# source_eagle.net
KiCad netlist of a schematic drawn in EAGLE
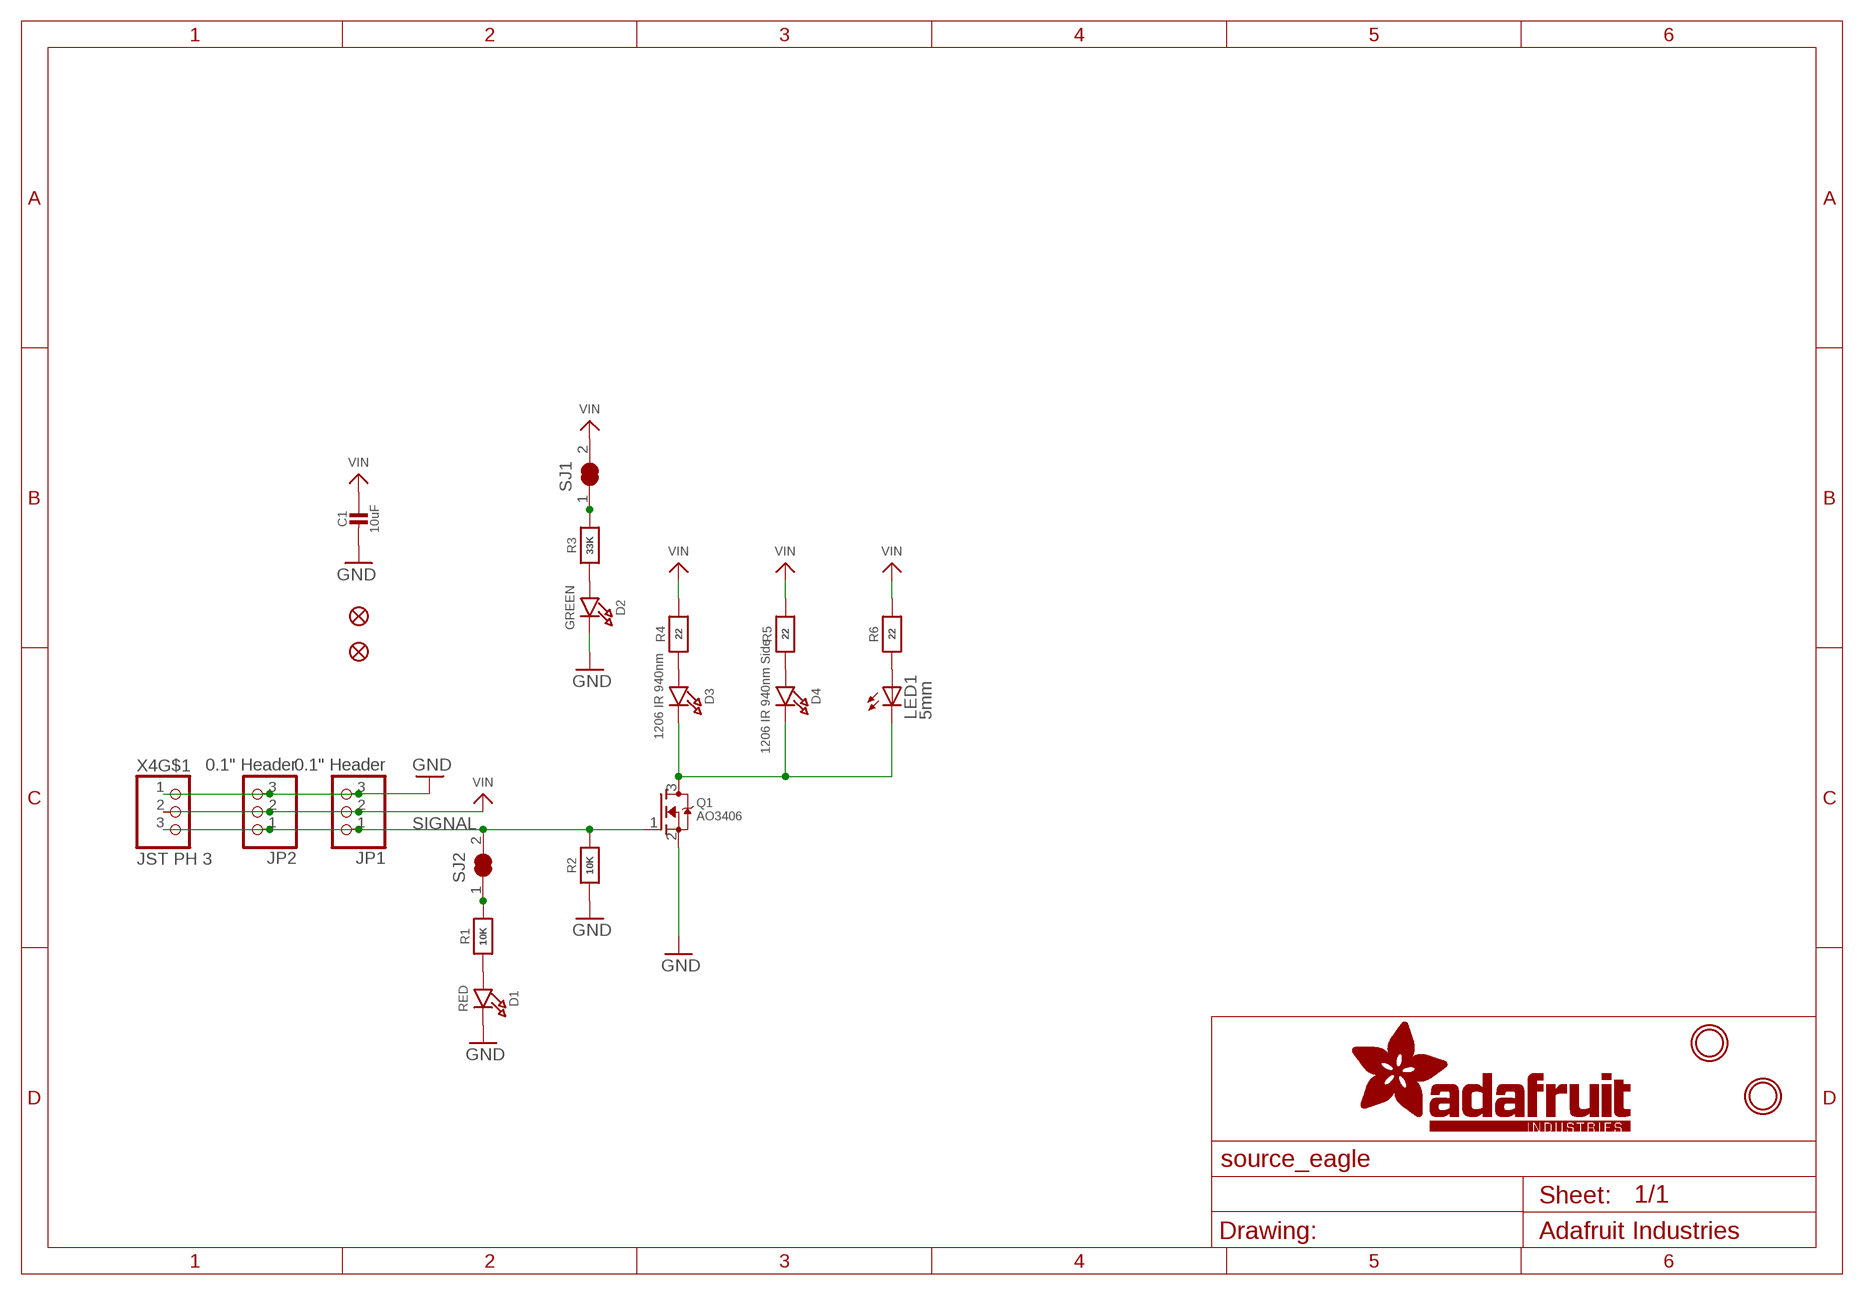
[diagram p0: schematic, sheet 1]

(export (version "E")
  (design (tool "Eeschema 10.0.6"))
  (components
    (comp (ref "C1")
      (value "10uF")
      (footprint "eagle-import:0805-NO")
      (libsource (lib "eagle-import") (part "CAP_CERAMIC0805-NOOUTLINE"))
    )
    (comp (ref "D1")
      (value "RED")
      (footprint "eagle-import:CHIPLED_0603_NOOUTLINE")
      (libsource (lib "eagle-import") (part "LED0603_NOOUTLINE"))
    )
    (comp (ref "D2")
      (value "GREEN")
      (footprint "eagle-import:CHIPLED_0603_NOOUTLINE")
      (libsource (lib "eagle-import") (part "LED0603_NOOUTLINE"))
    )
    (comp (ref "D3")
      (value "1206 IR 940nm")
      (footprint "eagle-import:CHIPLED_1206")
      (libsource (lib "eagle-import") (part "LED1206"))
    )
    (comp (ref "D4")
      (value "1206 IR 940nm Side")
      (footprint "eagle-import:LED_1206_SIDE")
      (libsource (lib "eagle-import") (part "LED_1206RA"))
    )
    (comp (ref "FID2")
      (value "FIDUCIAL_1MM")
      (footprint "eagle-import:FIDUCIAL_1MM")
      (libsource (lib "eagle-import") (part "FIDUCIAL_1MM"))
    )
    (comp (ref "FID3")
      (value "FIDUCIAL_1MM")
      (footprint "eagle-import:FIDUCIAL_1MM")
      (libsource (lib "eagle-import") (part "FIDUCIAL_1MM"))
    )
    (comp (ref "JP1")
      (value "0.1\" Header")
      (footprint "eagle-import:1X03_OVAL")
      (libsource (lib "eagle-import") (part "HEADER-1X3"))
    )
    (comp (ref "JP2")
      (value "0.1\" Header")
      (footprint "eagle-import:1X03_ROUND")
      (libsource (lib "eagle-import") (part "HEADER-1X3ROUND"))
    )
    (comp (ref "LED1")
      (value "5mm")
      (footprint "eagle-import:LED5MM")
      (libsource (lib "eagle-import") (part "LED5MM"))
    )
    (comp (ref "Q1")
      (value "AO3406")
      (footprint "eagle-import:SOT23-WIDE")
      (libsource (lib "eagle-import") (part "MOSFET-NWIDE"))
    )
    (comp (ref "R1")
      (value "10K")
      (footprint "eagle-import:0603-NO")
      (libsource (lib "eagle-import") (part "RESISTOR_0603_NOOUT"))
    )
    (comp (ref "R2")
      (value "10K")
      (footprint "eagle-import:0603-NO")
      (libsource (lib "eagle-import") (part "RESISTOR_0603_NOOUT"))
    )
    (comp (ref "R3")
      (value "33K")
      (footprint "eagle-import:0603-NO")
      (libsource (lib "eagle-import") (part "RESISTOR_0603_NOOUT"))
    )
    (comp (ref "R4")
      (value "22")
      (footprint "eagle-import:0603-NO")
      (libsource (lib "eagle-import") (part "RESISTOR_0603_NOOUT"))
    )
    (comp (ref "R5")
      (value "22")
      (footprint "eagle-import:0603-NO")
      (libsource (lib "eagle-import") (part "RESISTOR_0603_NOOUT"))
    )
    (comp (ref "R6")
      (value "22")
      (footprint "eagle-import:0603-NO")
      (libsource (lib "eagle-import") (part "RESISTOR_0603_NOOUT"))
    )
    (comp (ref "SJ1")
      (value "SOLDERJUMPER_CLOSED")
      (footprint "eagle-import:SOLDERJUMPER_CLOSEDWIRE")
      (libsource (lib "eagle-import") (part "SOLDERJUMPER_CLOSED"))
    )
    (comp (ref "SJ2")
      (value "SOLDERJUMPER_CLOSED")
      (footprint "eagle-import:SOLDERJUMPER_CLOSEDWIRE")
      (libsource (lib "eagle-import") (part "SOLDERJUMPER_CLOSED"))
    )
    (comp (ref "U$1")
      (value "MOUNTINGHOLE2.5")
      (footprint "eagle-import:MOUNTINGHOLE_2.5_PLATED")
      (libsource (lib "eagle-import") (part "MOUNTINGHOLE2.5"))
    )
    (comp (ref "U$8")
      (value "MOUNTINGHOLE2.5")
      (footprint "eagle-import:MOUNTINGHOLE_2.5_PLATED")
      (libsource (lib "eagle-import") (part "MOUNTINGHOLE2.5"))
    )
    (comp (ref "X4")
      (value "JST PH 3")
      (footprint "eagle-import:JSTPH3")
      (libsource (lib "eagle-import") (part "CON_JST_PH_3PIN"))
    )
  )
  (nets
    (net (code "1") (name "/SIGNAL") (class "Default")
      (node (ref "JP1") (pin "1") (pinfunction "1_1") (pintype "passive"))
      (node (ref "JP2") (pin "1") (pinfunction "1_1") (pintype "passive"))
      (node (ref "Q1") (pin "1") (pinfunction "G_1") (pintype "bidirectional"))
      (node (ref "R2") (pin "2") (pinfunction "2_2") (pintype "passive"))
      (node (ref "SJ2") (pin "2") (pinfunction "2_2") (pintype "passive"))
      (node (ref "X4") (pin "3") (pinfunction "3_3") (pintype "passive"))
    )
    (net (code "2") (name "GND") (class "Default")
      (node (ref "C1") (pin "2") (pinfunction "2_2") (pintype "passive"))
      (node (ref "D1") (pin "C") (pinfunction "C_C") (pintype "passive"))
      (node (ref "D2") (pin "C") (pinfunction "C_C") (pintype "passive"))
      (node (ref "JP1") (pin "3") (pinfunction "3_3") (pintype "passive"))
      (node (ref "JP2") (pin "3") (pinfunction "3_3") (pintype "passive"))
      (node (ref "Q1") (pin "2") (pinfunction "S_2") (pintype "bidirectional"))
      (node (ref "R2") (pin "1") (pinfunction "1_1") (pintype "passive"))
      (node (ref "X4") (pin "1") (pinfunction "1_1") (pintype "passive"))
    )
    (net (code "3") (name "Net-(D1-PadA)") (class "Default")
      (node (ref "D1") (pin "A") (pinfunction "A_A") (pintype "passive"))
      (node (ref "R1") (pin "1") (pinfunction "1_1") (pintype "passive"))
    )
    (net (code "4") (name "Net-(D2-PadA)") (class "Default")
      (node (ref "D2") (pin "A") (pinfunction "A_A") (pintype "passive"))
      (node (ref "R3") (pin "1") (pinfunction "1_1") (pintype "passive"))
    )
    (net (code "5") (name "Net-(D3-PadA)") (class "Default")
      (node (ref "D3") (pin "A") (pinfunction "A_A") (pintype "passive"))
      (node (ref "R4") (pin "1") (pinfunction "1_1") (pintype "passive"))
    )
    (net (code "6") (name "Net-(D4-PadA)") (class "Default")
      (node (ref "D4") (pin "A") (pinfunction "A_A") (pintype "passive"))
      (node (ref "R5") (pin "1") (pinfunction "1_1") (pintype "passive"))
    )
    (net (code "7") (name "Net-(LED1-C)") (class "Default")
      (node (ref "D3") (pin "C") (pinfunction "C_C") (pintype "passive"))
      (node (ref "D4") (pin "C") (pinfunction "C_C") (pintype "passive"))
      (node (ref "LED1") (pin "K") (pinfunction "C_K") (pintype "passive"))
      (node (ref "Q1") (pin "3") (pinfunction "D_3") (pintype "bidirectional"))
    )
    (net (code "8") (name "Net-(LED1-PadA)") (class "Default")
      (node (ref "LED1") (pin "A") (pinfunction "A_A") (pintype "passive"))
      (node (ref "R6") (pin "1") (pinfunction "1_1") (pintype "passive"))
    )
    (net (code "9") (name "Net-(R1-Pad2)") (class "Default")
      (node (ref "R1") (pin "2") (pinfunction "2_2") (pintype "passive"))
      (node (ref "SJ2") (pin "1") (pinfunction "1_1") (pintype "passive"))
    )
    (net (code "10") (name "Net-(R3-Pad2)") (class "Default")
      (node (ref "R3") (pin "2") (pinfunction "2_2") (pintype "passive"))
      (node (ref "SJ1") (pin "1") (pinfunction "1_1") (pintype "passive"))
    )
    (net (code "11") (name "VIN") (class "Default")
      (node (ref "C1") (pin "1") (pinfunction "1_1") (pintype "passive"))
      (node (ref "JP1") (pin "2") (pinfunction "2_2") (pintype "passive"))
      (node (ref "JP2") (pin "2") (pinfunction "2_2") (pintype "passive"))
      (node (ref "R4") (pin "2") (pinfunction "2_2") (pintype "passive"))
      (node (ref "R5") (pin "2") (pinfunction "2_2") (pintype "passive"))
      (node (ref "R6") (pin "2") (pinfunction "2_2") (pintype "passive"))
      (node (ref "SJ1") (pin "2") (pinfunction "2_2") (pintype "passive"))
      (node (ref "X4") (pin "2") (pinfunction "2_2") (pintype "passive"))
    )
  )
)
